# FMC_HPC1.net
KiCad netlist of a schematic drawn in Altium Designer
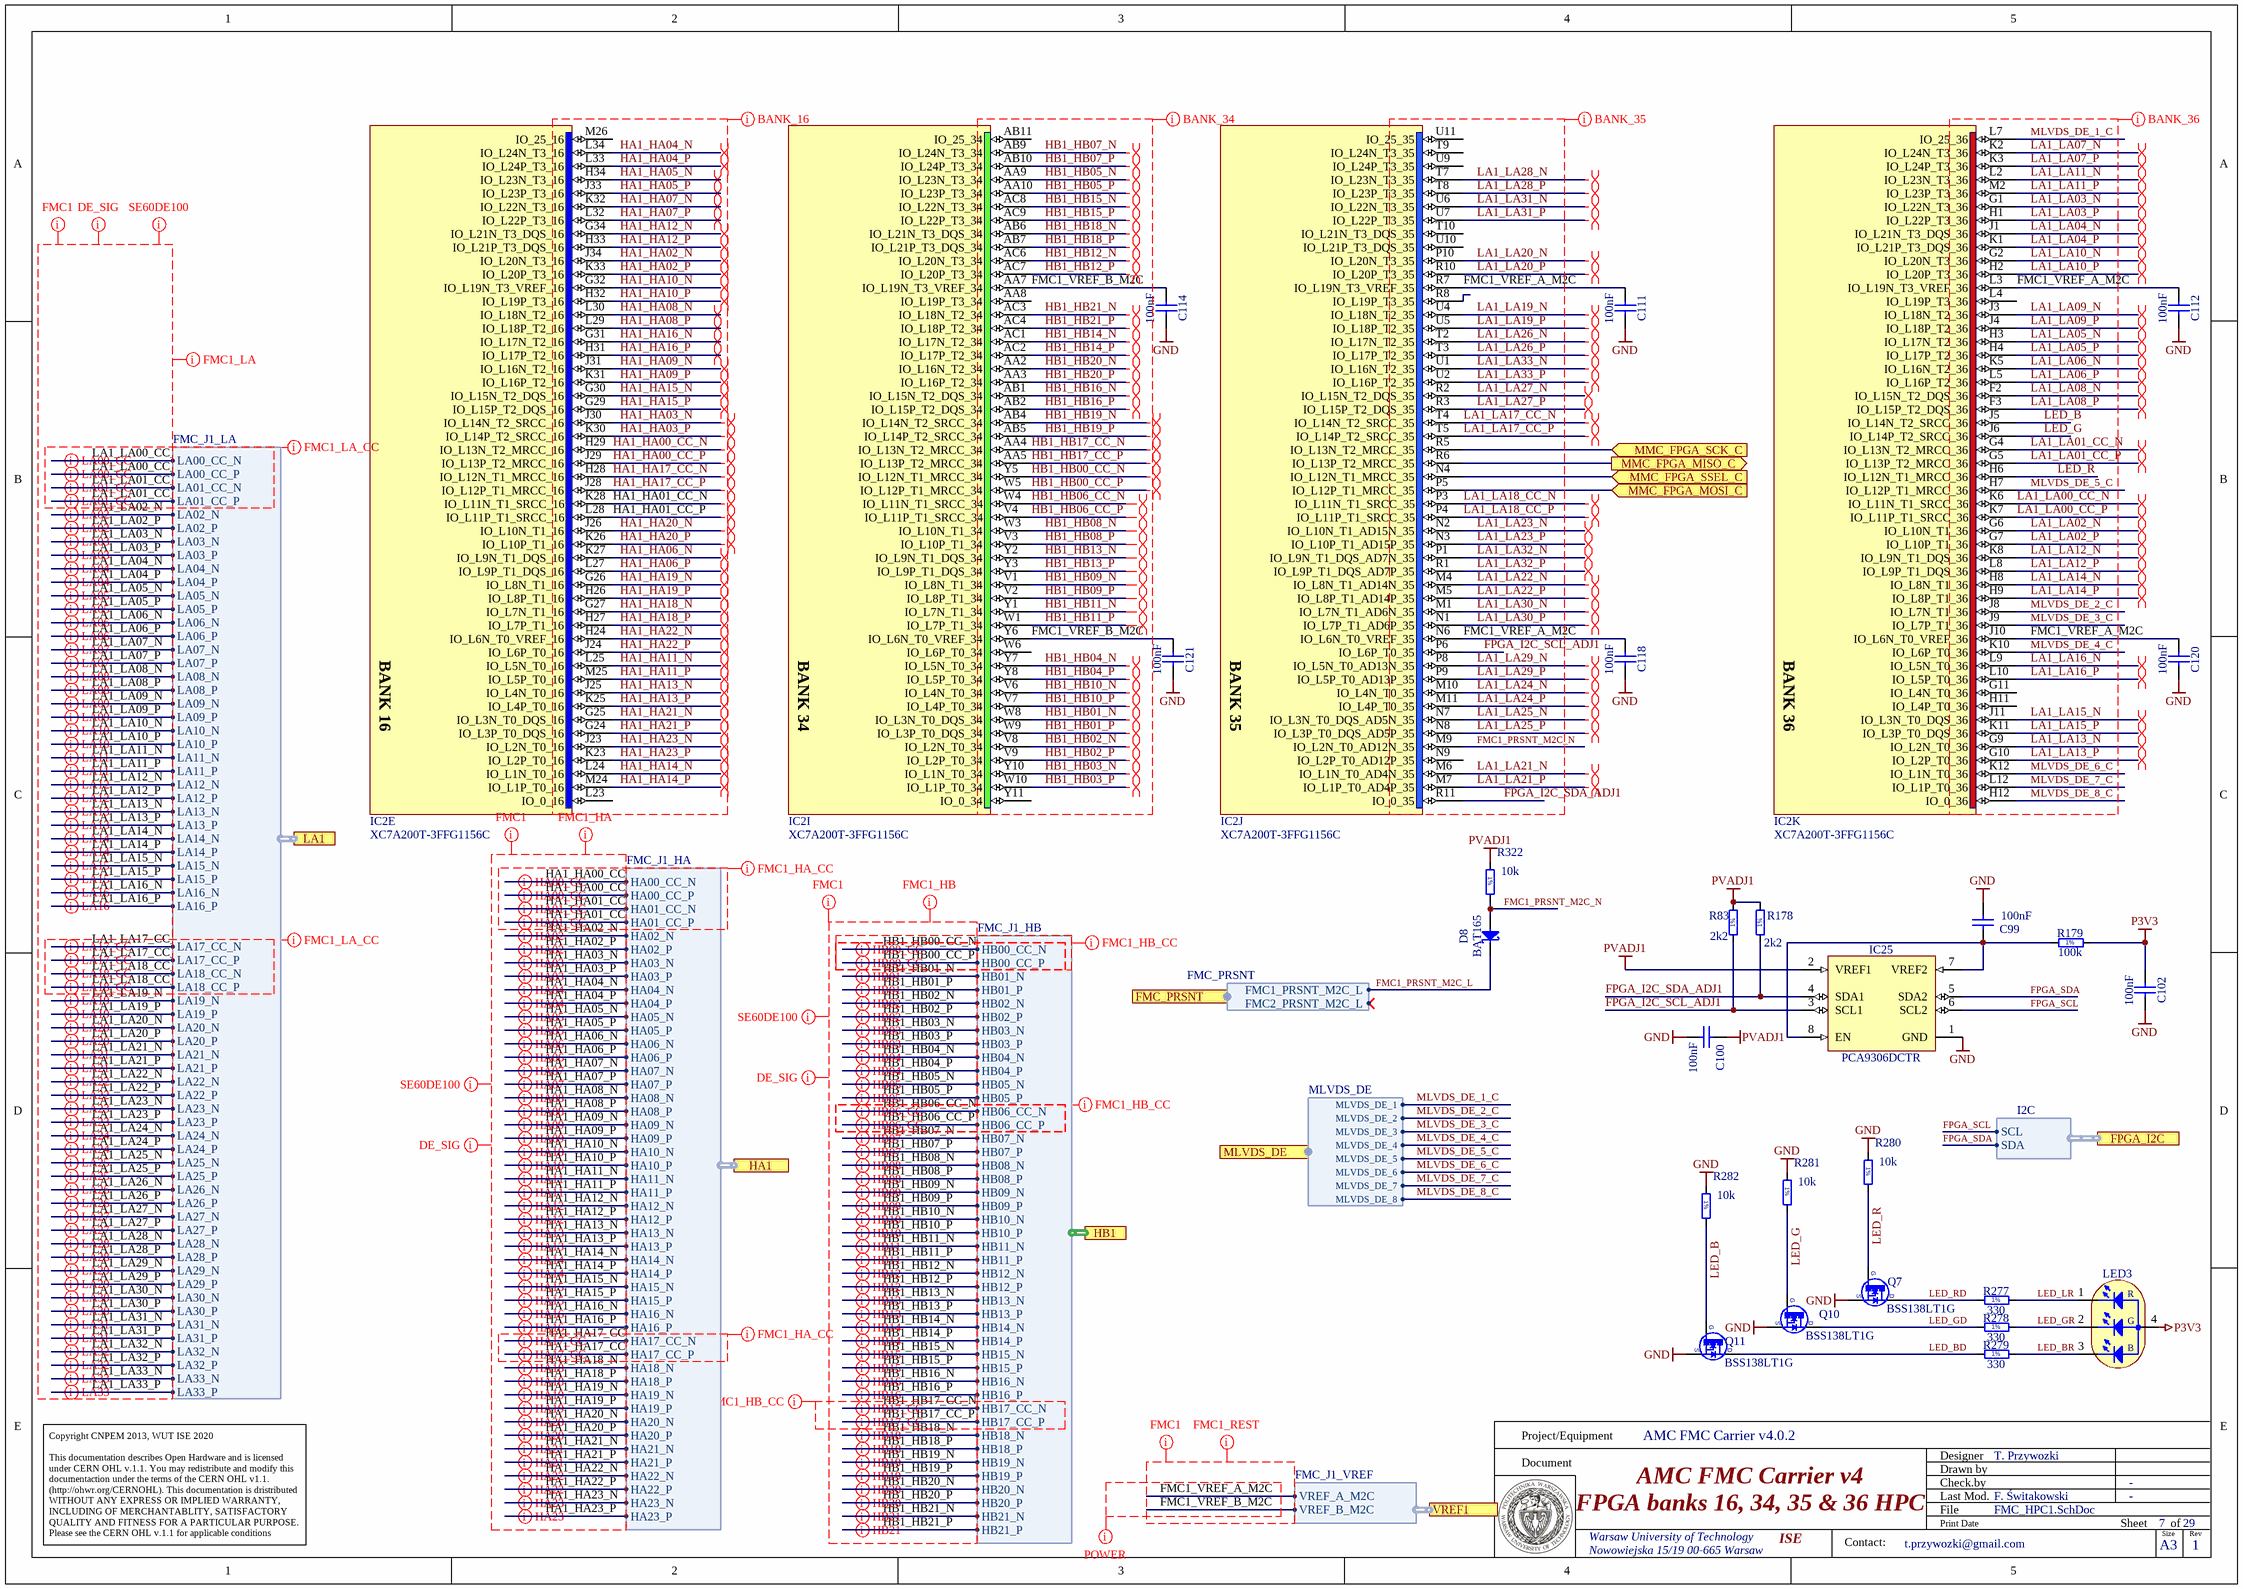
[diagram p0: FMC_HPC1.SchDoc]

(export (version "E")
  (design (tool "Eeschema 10.0.6"))
  (components
    (comp (ref "C99")
      (value "100nF")
      (footprint "CAPC0603X33N")
      (description "Non-polarised capacitor")
      (fields
        (field (name "PART NUMBER") "CC0201_100NF_6.3V_10%_X5R")
        (field (name "VOLTAGE") "6.3V")
        (field (name "AUTHOR") "CERN DEM JLC")
      )
      (libsource (lib "Capacitors") (part "Capacitor - non polarized"))
    )
    (comp (ref "C100")
      (value "100nF")
      (footprint "CAPC0603X33N")
      (description "Non-polarised capacitor")
      (fields
        (field (name "PART NUMBER") "CC0201_100NF_6.3V_10%_X5R")
        (field (name "VOLTAGE") "6.3V")
        (field (name "AUTHOR") "CERN DEM JLC")
      )
      (libsource (lib "Capacitors") (part "Capacitor - non polarized"))
    )
    (comp (ref "C102")
      (value "100nF")
      (footprint "CAPC0603X33N")
      (description "Non-polarised capacitor")
      (fields
        (field (name "PART NUMBER") "CC0201_100NF_6.3V_10%_X5R")
        (field (name "VOLTAGE") "6.3V")
        (field (name "AUTHOR") "CERN DEM JLC")
      )
      (libsource (lib "Capacitors") (part "Capacitor - non polarized"))
    )
    (comp (ref "C111")
      (value "100nF")
      (footprint "CAPC0603X33N")
      (description "Non-polarised capacitor")
      (fields
        (field (name "PART NUMBER") "CC0201_100NF_6.3V_10%_X5R")
        (field (name "VOLTAGE") "6.3V")
        (field (name "AUTHOR") "CERN DEM JLC")
      )
      (libsource (lib "Capacitors") (part "Capacitor - non polarized"))
    )
    (comp (ref "C112")
      (value "100nF")
      (footprint "CAPC0603X33N")
      (description "Non-polarised capacitor")
      (fields
        (field (name "PART NUMBER") "CC0201_100NF_6.3V_10%_X5R")
        (field (name "VOLTAGE") "6.3V")
        (field (name "AUTHOR") "CERN DEM JLC")
      )
      (libsource (lib "Capacitors") (part "Capacitor - non polarized"))
    )
    (comp (ref "C114")
      (value "100nF")
      (footprint "CAPC0603X33N")
      (description "Non-polarised capacitor")
      (fields
        (field (name "PART NUMBER") "CC0201_100NF_6.3V_10%_X5R")
        (field (name "VOLTAGE") "6.3V")
        (field (name "AUTHOR") "CERN DEM JLC")
      )
      (libsource (lib "Capacitors") (part "Capacitor - non polarized"))
    )
    (comp (ref "C118")
      (value "100nF")
      (footprint "CAPC0603X33N")
      (description "Non-polarised capacitor")
      (fields
        (field (name "PART NUMBER") "CC0201_100NF_6.3V_10%_X5R")
        (field (name "VOLTAGE") "6.3V")
        (field (name "AUTHOR") "CERN DEM JLC")
      )
      (libsource (lib "Capacitors") (part "Capacitor - non polarized"))
    )
    (comp (ref "C120")
      (value "100nF")
      (footprint "CAPC0603X33N")
      (description "Non-polarised capacitor")
      (fields
        (field (name "PART NUMBER") "CC0201_100NF_6.3V_10%_X5R")
        (field (name "VOLTAGE") "6.3V")
        (field (name "AUTHOR") "CERN DEM JLC")
      )
      (libsource (lib "Capacitors") (part "Capacitor - non polarized"))
    )
    (comp (ref "C121")
      (value "100nF")
      (footprint "CAPC0603X33N")
      (description "Non-polarised capacitor")
      (fields
        (field (name "PART NUMBER") "CC0201_100NF_6.3V_10%_X5R")
        (field (name "VOLTAGE") "6.3V")
        (field (name "AUTHOR") "CERN DEM JLC")
      )
      (libsource (lib "Capacitors") (part "Capacitor - non polarized"))
    )
    (comp (ref "D8")
      (value "BAT165")
      (footprint "SOD2512X110N")
      (description "Schottky Diode")
      (fields
        (field (name "MANUFACTURER") "INFINEON")
        (field (name "VOLTAGE") "40V")
        (field (name "AUTHOR") "CERN DEM JLC")
      )
      (libsource (lib "ICs And Semiconductors") (part "Diode Schottky"))
    )
    (comp (ref "IC2")
      (value "XC7A200T-3FFG1156C")
      (footprint "BGA1156C100P34X34_3500X3500X335")
      (description "Artix-6 FPGA, 16 GTPs, 600 User I/Os, 1156-Pin BGA, Speed Grade 2, Commercial Grade, Pb-Free")
      (fields
        (field (name "MANUFACTURER") "XILINX")
        (field (name "MANUFACTURER PART NUMBER") "XC7A350T-2FFG1156C")
        (field (name "AUTHOR") "CERN DEM JLC")
      )
      (libsource (lib "AMC_FMC_Carrier") (part "XC7A200T-3FFG1156C"))
    )
    (comp (ref "IC25")
      (value "PCA9306DCTR")
      (footprint "SOP65P400X130-8N")
      (description "Dual Bidirectional I2C Bus And SMBus Voltage-Level Translator")
      (fields (field (name "MANUFACTURER") "TEXAS INSTRUMENTS") (field (name "AUTHOR") "CERN DEM JLC"))
      (libsource (lib "ICs And Semiconductors") (part "PCA9306DC"))
    )
    (comp (ref "LED3")
      (value "Red/Green/Blue")
      (footprint "LED_OPTEK_OVSRRGBCC3_a")
      (description "Right Angle Tricolor (RGB) Surface Mount LED, Body 3.2x1mm")
      (fields
        (field (name "PART NUMBER") "LED_OPTEK_OVSRRGBCC3_a")
        (field (name "MANUFACTURER") "OPTEK / TT ELECTRONICS")
        (field (name "AUTHOR") "CERN DEM JLC")
      )
      (libsource (lib "ICs And Semiconductors") (part "LED_OPTEK_OVSRRGBCC3"))
    )
    (comp (ref "Q7")
      (value "BSS138LT1G")
      (footprint "SOT95P240X110-3N")
      (description "N-CHANNEL MOSFET WITH DIODE")
      (fields (field (name "MANUFACTURER") "ON SEMICONDUCTOR") (field (name "AUTHOR") "CERN DEM JLC"))
      (libsource (lib "ICs And Semiconductors") (part "N-MOSFET-D 1G 2S 3D"))
    )
    (comp (ref "Q10")
      (value "BSS138LT1G")
      (footprint "SOT95P240X110-3N")
      (description "N-CHANNEL MOSFET WITH DIODE")
      (fields (field (name "MANUFACTURER") "ON SEMICONDUCTOR") (field (name "AUTHOR") "CERN DEM JLC"))
      (libsource (lib "ICs And Semiconductors") (part "N-MOSFET-D 1G 2S 3D"))
    )
    (comp (ref "Q11")
      (value "BSS138LT1G")
      (footprint "SOT95P240X110-3N")
      (description "N-CHANNEL MOSFET WITH DIODE")
      (fields (field (name "MANUFACTURER") "ON SEMICONDUCTOR") (field (name "AUTHOR") "CERN DEM JLC"))
      (libsource (lib "ICs And Semiconductors") (part "N-MOSFET-D 1G 2S 3D"))
    )
    (comp (ref "R83")
      (value "2k2")
      (footprint "RESC1005X40N")
      (description "Resistor - 1%")
      (fields
        (field (name "PART NUMBER") "R0402_2K2_1%_0.0625W_100PPM")
        (field (name "POWER") "0.0625W")
        (field (name "AUTHOR") "CERN DEM JLC")
      )
      (libsource (lib "Resistors") (part "Resistor - 1%"))
    )
    (comp (ref "R178")
      (value "2k2")
      (footprint "RESC1005X40N")
      (description "Resistor - 1%")
      (fields
        (field (name "PART NUMBER") "R0402_2K2_1%_0.0625W_100PPM")
        (field (name "POWER") "0.0625W")
        (field (name "AUTHOR") "CERN DEM JLC")
      )
      (libsource (lib "Resistors") (part "Resistor - 1%"))
    )
    (comp (ref "R179")
      (value "100k")
      (footprint "RESC1005X40N")
      (description "Resistor - 1%")
      (fields
        (field (name "PART NUMBER") "R0402_100K_1%_0.0625W_100PPM")
        (field (name "POWER") "0.0625W")
        (field (name "AUTHOR") "CERN DEM JLC")
      )
      (libsource (lib "Resistors") (part "Resistor - 1%"))
    )
    (comp (ref "R277")
      (value "330")
      (footprint "RESC1005X40N")
      (description "Resistor - 1%")
      (fields
        (field (name "PART NUMBER") "R0402_330R_1%_0.0625W_100PPM")
        (field (name "POWER") "0.0625W")
        (field (name "AUTHOR") "CERN DEM JLC")
      )
      (libsource (lib "Resistors") (part "Resistor - 1%"))
    )
    (comp (ref "R278")
      (value "330")
      (footprint "RESC1005X40N")
      (description "Resistor - 1%")
      (fields
        (field (name "PART NUMBER") "R0402_330R_1%_0.0625W_100PPM")
        (field (name "POWER") "0.0625W")
        (field (name "AUTHOR") "CERN DEM JLC")
      )
      (libsource (lib "Resistors") (part "Resistor - 1%"))
    )
    (comp (ref "R279")
      (value "330")
      (footprint "RESC1005X40N")
      (description "Resistor - 1%")
      (fields
        (field (name "PART NUMBER") "R0402_330R_1%_0.0625W_100PPM")
        (field (name "POWER") "0.0625W")
        (field (name "AUTHOR") "CERN DEM JLC")
      )
      (libsource (lib "Resistors") (part "Resistor - 1%"))
    )
    (comp (ref "R280")
      (value "10k")
      (footprint "RESC1005X40N")
      (description "Resistor - 1%")
      (fields
        (field (name "PART NUMBER") "R0402_10K_1%_0.0625W_100PPM")
        (field (name "POWER") "0.0625W")
        (field (name "AUTHOR") "CERN DEM JLC")
      )
      (libsource (lib "Resistors") (part "Resistor - 1%"))
    )
    (comp (ref "R281")
      (value "10k")
      (footprint "RESC1005X40N")
      (description "Resistor - 1%")
      (fields
        (field (name "PART NUMBER") "R0402_10K_1%_0.0625W_100PPM")
        (field (name "POWER") "0.0625W")
        (field (name "AUTHOR") "CERN DEM JLC")
      )
      (libsource (lib "Resistors") (part "Resistor - 1%"))
    )
    (comp (ref "R282")
      (value "10k")
      (footprint "RESC1005X40N")
      (description "Resistor - 1%")
      (fields
        (field (name "PART NUMBER") "R0402_10K_1%_0.0625W_100PPM")
        (field (name "POWER") "0.0625W")
        (field (name "AUTHOR") "CERN DEM JLC")
      )
      (libsource (lib "Resistors") (part "Resistor - 1%"))
    )
    (comp (ref "R322")
      (value "10k")
      (footprint "RESC1005X40N")
      (description "Resistor - 1%")
      (fields
        (field (name "PART NUMBER") "R0402_10K_1%_0.0625W_100PPM")
        (field (name "POWER") "0.0625W")
        (field (name "AUTHOR") "CERN DEM JLC")
      )
      (libsource (lib "Resistors") (part "Resistor - 1%"))
    )
  )
  (nets
    (net (code "8") (name "/FMC1_PRSNT_M2C_L") (class "Default")
      (node (ref "D8") (pin "1") (pinfunction "C_1") (pintype "passive"))
    )
    (net (code "9") (name "/FMC1_PRSNT_M2C_N") (class "Default")
      (node (ref "D8") (pin "2") (pinfunction "A_2") (pintype "passive"))
      (node (ref "IC2") (pin "M9") (pinfunction "IO_L2N_T0_AD12N_35_M9") (pintype "bidirectional"))
      (node (ref "R322") (pin "2") (pinfunction "2_2") (pintype "passive"))
    )
    (net (code "10") (name "/FMC1_VREF_A_M2C") (class "Default")
      (node (ref "C111") (pin "1") (pinfunction "1_1") (pintype "passive"))
      (node (ref "C112") (pin "1") (pinfunction "1_1") (pintype "passive"))
      (node (ref "C118") (pin "1") (pinfunction "1_1") (pintype "passive"))
      (node (ref "C120") (pin "1") (pinfunction "1_1") (pintype "passive"))
      (node (ref "IC2") (pin "J10") (pinfunction "IO_L6N_T0_VREF_36_J10") (pintype "bidirectional"))
      (node (ref "IC2") (pin "L3") (pinfunction "IO_L19N_T3_VREF_36_L3") (pintype "bidirectional"))
      (node (ref "IC2") (pin "N6") (pinfunction "IO_L6N_T0_VREF_35_N6") (pintype "bidirectional"))
      (node (ref "IC2") (pin "R7") (pinfunction "IO_L19N_T3_VREF_35_R7") (pintype "bidirectional"))
    )
    (net (code "11") (name "/FMC1_VREF_B_M2C") (class "Default")
      (node (ref "C114") (pin "1") (pinfunction "1_1") (pintype "passive"))
      (node (ref "C121") (pin "1") (pinfunction "1_1") (pintype "passive"))
      (node (ref "IC2") (pin "AA7") (pinfunction "IO_L19N_T3_VREF_34_AA7") (pintype "bidirectional"))
      (node (ref "IC2") (pin "Y6") (pinfunction "IO_L6N_T0_VREF_34_Y6") (pintype "bidirectional"))
    )
    (net (code "12") (name "/FPGA_I2C_SCL_ADJ1") (class "Default")
      (node (ref "IC2") (pin "P6") (pinfunction "IO_L6P_T0_35_P6") (pintype "bidirectional"))
      (node (ref "IC25") (pin "3") (pinfunction "SCL1_3") (pintype "bidirectional"))
      (node (ref "R83") (pin "1") (pinfunction "1_1") (pintype "passive"))
    )
    (net (code "13") (name "/FPGA_I2C_SDA_ADJ1") (class "Default")
      (node (ref "IC2") (pin "R11") (pinfunction "IO_0_35_R11") (pintype "bidirectional"))
      (node (ref "IC25") (pin "4") (pinfunction "SDA1_4") (pintype "bidirectional"))
      (node (ref "R178") (pin "1") (pinfunction "1_1") (pintype "passive"))
    )
    (net (code "14") (name "/FPGA_SCL") (class "Default")
      (node (ref "IC25") (pin "6") (pinfunction "SCL2_6") (pintype "bidirectional"))
    )
    (net (code "15") (name "/FPGA_SDA") (class "Default")
      (node (ref "IC25") (pin "5") (pinfunction "SDA2_5") (pintype "bidirectional"))
    )
    (net (code "16") (name "/HA1_HA00_CC_N") (class "Default")
      (node (ref "IC2") (pin "H29") (pinfunction "IO_L13N_T2_MRCC_16_H29") (pintype "bidirectional"))
    )
    (net (code "17") (name "/HA1_HA00_CC_P") (class "Default")
      (node (ref "IC2") (pin "J29") (pinfunction "IO_L13P_T2_MRCC_16_J29") (pintype "bidirectional"))
    )
    (net (code "18") (name "/HA1_HA01_CC_N") (class "Default")
      (node (ref "IC2") (pin "K28") (pinfunction "IO_L11N_T1_SRCC_16_K28") (pintype "bidirectional"))
    )
    (net (code "19") (name "/HA1_HA01_CC_P") (class "Default")
      (node (ref "IC2") (pin "L28") (pinfunction "IO_L11P_T1_SRCC_16_L28") (pintype "bidirectional"))
    )
    (net (code "20") (name "/HA1_HA02_N") (class "Default")
      (node (ref "IC2") (pin "J34") (pinfunction "IO_L20N_T3_16_J34") (pintype "bidirectional"))
    )
    (net (code "21") (name "/HA1_HA02_P") (class "Default")
      (node (ref "IC2") (pin "K33") (pinfunction "IO_L20P_T3_16_K33") (pintype "bidirectional"))
    )
    (net (code "22") (name "/HA1_HA03_N") (class "Default")
      (node (ref "IC2") (pin "J30") (pinfunction "IO_L14N_T2_SRCC_16_J30") (pintype "bidirectional"))
    )
    (net (code "23") (name "/HA1_HA03_P") (class "Default")
      (node (ref "IC2") (pin "K30") (pinfunction "IO_L14P_T2_SRCC_16_K30") (pintype "bidirectional"))
    )
    (net (code "24") (name "/HA1_HA04_N") (class "Default")
      (node (ref "IC2") (pin "L34") (pinfunction "IO_L24N_T3_16_L34") (pintype "bidirectional"))
    )
    (net (code "25") (name "/HA1_HA04_P") (class "Default")
      (node (ref "IC2") (pin "L33") (pinfunction "IO_L24P_T3_16_L33") (pintype "bidirectional"))
    )
    (net (code "26") (name "/HA1_HA05_N") (class "Default")
      (node (ref "IC2") (pin "H34") (pinfunction "IO_L23N_T3_16_H34") (pintype "bidirectional"))
    )
    (net (code "27") (name "/HA1_HA05_P") (class "Default")
      (node (ref "IC2") (pin "J33") (pinfunction "IO_L23P_T3_16_J33") (pintype "bidirectional"))
    )
    (net (code "28") (name "/HA1_HA06_N") (class "Default")
      (node (ref "IC2") (pin "K27") (pinfunction "IO_L9N_T1_DQS_16_K27") (pintype "bidirectional"))
    )
    (net (code "29") (name "/HA1_HA06_P") (class "Default")
      (node (ref "IC2") (pin "L27") (pinfunction "IO_L9P_T1_DQS_16_L27") (pintype "bidirectional"))
    )
    (net (code "30") (name "/HA1_HA07_N") (class "Default")
      (node (ref "IC2") (pin "K32") (pinfunction "IO_L22N_T3_16_K32") (pintype "bidirectional"))
    )
    (net (code "31") (name "/HA1_HA07_P") (class "Default")
      (node (ref "IC2") (pin "L32") (pinfunction "IO_L22P_T3_16_L32") (pintype "bidirectional"))
    )
    (net (code "32") (name "/HA1_HA08_N") (class "Default")
      (node (ref "IC2") (pin "L30") (pinfunction "IO_L18N_T2_16_L30") (pintype "bidirectional"))
    )
    (net (code "33") (name "/HA1_HA08_P") (class "Default")
      (node (ref "IC2") (pin "L29") (pinfunction "IO_L18P_T2_16_L29") (pintype "bidirectional"))
    )
    (net (code "34") (name "/HA1_HA09_N") (class "Default")
      (node (ref "IC2") (pin "J31") (pinfunction "IO_L16N_T2_16_J31") (pintype "bidirectional"))
    )
    (net (code "35") (name "/HA1_HA09_P") (class "Default")
      (node (ref "IC2") (pin "K31") (pinfunction "IO_L16P_T2_16_K31") (pintype "bidirectional"))
    )
    (net (code "36") (name "/HA1_HA10_N") (class "Default")
      (node (ref "IC2") (pin "G32") (pinfunction "IO_L19N_T3_VREF_16_G32") (pintype "bidirectional"))
    )
    (net (code "37") (name "/HA1_HA10_P") (class "Default")
      (node (ref "IC2") (pin "H32") (pinfunction "IO_L19P_T3_16_H32") (pintype "bidirectional"))
    )
    (net (code "38") (name "/HA1_HA11_N") (class "Default")
      (node (ref "IC2") (pin "L25") (pinfunction "IO_L5N_T0_16_L25") (pintype "bidirectional"))
    )
    (net (code "39") (name "/HA1_HA11_P") (class "Default")
      (node (ref "IC2") (pin "M25") (pinfunction "IO_L5P_T0_16_M25") (pintype "bidirectional"))
    )
    (net (code "40") (name "/HA1_HA12_N") (class "Default")
      (node (ref "IC2") (pin "G34") (pinfunction "IO_L21N_T3_DQS_16_G34") (pintype "bidirectional"))
    )
    (net (code "41") (name "/HA1_HA12_P") (class "Default")
      (node (ref "IC2") (pin "H33") (pinfunction "IO_L21P_T3_DQS_16_H33") (pintype "bidirectional"))
    )
    (net (code "42") (name "/HA1_HA13_N") (class "Default")
      (node (ref "IC2") (pin "J25") (pinfunction "IO_L4N_T0_16_J25") (pintype "bidirectional"))
    )
    (net (code "43") (name "/HA1_HA13_P") (class "Default")
      (node (ref "IC2") (pin "K25") (pinfunction "IO_L4P_T0_16_K25") (pintype "bidirectional"))
    )
    (net (code "44") (name "/HA1_HA14_N") (class "Default")
      (node (ref "IC2") (pin "L24") (pinfunction "IO_L1N_T0_16_L24") (pintype "bidirectional"))
    )
    (net (code "45") (name "/HA1_HA14_P") (class "Default")
      (node (ref "IC2") (pin "M24") (pinfunction "IO_L1P_T0_16_M24") (pintype "bidirectional"))
    )
    (net (code "46") (name "/HA1_HA15_N") (class "Default")
      (node (ref "IC2") (pin "G30") (pinfunction "IO_L15N_T2_DQS_16_G30") (pintype "bidirectional"))
    )
    (net (code "47") (name "/HA1_HA15_P") (class "Default")
      (node (ref "IC2") (pin "G29") (pinfunction "IO_L15P_T2_DQS_16_G29") (pintype "bidirectional"))
    )
    (net (code "48") (name "/HA1_HA16_N") (class "Default")
      (node (ref "IC2") (pin "G31") (pinfunction "IO_L17N_T2_16_G31") (pintype "bidirectional"))
    )
    (net (code "49") (name "/HA1_HA16_P") (class "Default")
      (node (ref "IC2") (pin "H31") (pinfunction "IO_L17P_T2_16_H31") (pintype "bidirectional"))
    )
    (net (code "50") (name "/HA1_HA17_CC_N") (class "Default")
      (node (ref "IC2") (pin "H28") (pinfunction "IO_L12N_T1_MRCC_16_H28") (pintype "bidirectional"))
    )
    (net (code "51") (name "/HA1_HA17_CC_P") (class "Default")
      (node (ref "IC2") (pin "J28") (pinfunction "IO_L12P_T1_MRCC_16_J28") (pintype "bidirectional"))
    )
    (net (code "52") (name "/HA1_HA18_N") (class "Default")
      (node (ref "IC2") (pin "G27") (pinfunction "IO_L7N_T1_16_G27") (pintype "bidirectional"))
    )
    (net (code "53") (name "/HA1_HA18_P") (class "Default")
      (node (ref "IC2") (pin "H27") (pinfunction "IO_L7P_T1_16_H27") (pintype "bidirectional"))
    )
    (net (code "54") (name "/HA1_HA19_N") (class "Default")
      (node (ref "IC2") (pin "G26") (pinfunction "IO_L8N_T1_16_G26") (pintype "bidirectional"))
    )
    (net (code "55") (name "/HA1_HA19_P") (class "Default")
      (node (ref "IC2") (pin "H26") (pinfunction "IO_L8P_T1_16_H26") (pintype "bidirectional"))
    )
    (net (code "56") (name "/HA1_HA20_N") (class "Default")
      (node (ref "IC2") (pin "J26") (pinfunction "IO_L10N_T1_16_J26") (pintype "bidirectional"))
    )
    (net (code "57") (name "/HA1_HA20_P") (class "Default")
      (node (ref "IC2") (pin "K26") (pinfunction "IO_L10P_T1_16_K26") (pintype "bidirectional"))
    )
    (net (code "58") (name "/HA1_HA21_N") (class "Default")
      (node (ref "IC2") (pin "G25") (pinfunction "IO_L3N_T0_DQS_16_G25") (pintype "bidirectional"))
    )
    (net (code "59") (name "/HA1_HA21_P") (class "Default")
      (node (ref "IC2") (pin "G24") (pinfunction "IO_L3P_T0_DQS_16_G24") (pintype "bidirectional"))
    )
    (net (code "60") (name "/HA1_HA22_N") (class "Default")
      (node (ref "IC2") (pin "H24") (pinfunction "IO_L6N_T0_VREF_16_H24") (pintype "bidirectional"))
    )
    (net (code "61") (name "/HA1_HA22_P") (class "Default")
      (node (ref "IC2") (pin "J24") (pinfunction "IO_L6P_T0_16_J24") (pintype "bidirectional"))
    )
    (net (code "62") (name "/HA1_HA23_N") (class "Default")
      (node (ref "IC2") (pin "J23") (pinfunction "IO_L2N_T0_16_J23") (pintype "bidirectional"))
    )
    (net (code "63") (name "/HA1_HA23_P") (class "Default")
      (node (ref "IC2") (pin "K23") (pinfunction "IO_L2P_T0_16_K23") (pintype "bidirectional"))
    )
    (net (code "64") (name "/HB1_HB00_CC_N") (class "Default")
      (node (ref "IC2") (pin "Y5") (pinfunction "IO_L12N_T1_MRCC_34_Y5") (pintype "bidirectional"))
    )
    (net (code "65") (name "/HB1_HB00_CC_P") (class "Default")
      (node (ref "IC2") (pin "W5") (pinfunction "IO_L12P_T1_MRCC_34_W5") (pintype "bidirectional"))
    )
    (net (code "66") (name "/HB1_HB01_N") (class "Default")
      (node (ref "IC2") (pin "W8") (pinfunction "IO_L3N_T0_DQS_34_W8") (pintype "bidirectional"))
    )
    (net (code "67") (name "/HB1_HB01_P") (class "Default")
      (node (ref "IC2") (pin "W9") (pinfunction "IO_L3P_T0_DQS_34_W9") (pintype "bidirectional"))
    )
    (net (code "68") (name "/HB1_HB02_N") (class "Default")
      (node (ref "IC2") (pin "V8") (pinfunction "IO_L2N_T0_34_V8") (pintype "bidirectional"))
    )
    (net (code "69") (name "/HB1_HB02_P") (class "Default")
      (node (ref "IC2") (pin "V9") (pinfunction "IO_L2P_T0_34_V9") (pintype "bidirectional"))
    )
    (net (code "70") (name "/HB1_HB03_N") (class "Default")
      (node (ref "IC2") (pin "Y10") (pinfunction "IO_L1N_T0_34_Y10") (pintype "bidirectional"))
    )
    (net (code "71") (name "/HB1_HB03_P") (class "Default")
      (node (ref "IC2") (pin "W10") (pinfunction "IO_L1P_T0_34_W10") (pintype "bidirectional"))
    )
    (net (code "72") (name "/HB1_HB04_N") (class "Default")
      (node (ref "IC2") (pin "Y7") (pinfunction "IO_L5N_T0_34_Y7") (pintype "bidirectional"))
    )
    (net (code "73") (name "/HB1_HB04_P") (class "Default")
      (node (ref "IC2") (pin "Y8") (pinfunction "IO_L5P_T0_34_Y8") (pintype "bidirectional"))
    )
    (net (code "74") (name "/HB1_HB05_N") (class "Default")
      (node (ref "IC2") (pin "AA9") (pinfunction "IO_L23N_T3_34_AA9") (pintype "bidirectional"))
    )
    (net (code "75") (name "/HB1_HB05_P") (class "Default")
      (node (ref "IC2") (pin "AA10") (pinfunction "IO_L23P_T3_34_AA10") (pintype "bidirectional"))
    )
    (net (code "76") (name "/HB1_HB06_CC_N") (class "Default")
      (node (ref "IC2") (pin "W4") (pinfunction "IO_L11N_T1_SRCC_34_W4") (pintype "bidirectional"))
    )
    (net (code "77") (name "/HB1_HB06_CC_P") (class "Default")
      (node (ref "IC2") (pin "V4") (pinfunction "IO_L11P_T1_SRCC_34_V4") (pintype "bidirectional"))
    )
    (net (code "78") (name "/HB1_HB07_N") (class "Default")
      (node (ref "IC2") (pin "AB9") (pinfunction "IO_L24N_T3_34_AB9") (pintype "bidirectional"))
    )
    (net (code "79") (name "/HB1_HB07_P") (class "Default")
      (node (ref "IC2") (pin "AB10") (pinfunction "IO_L24P_T3_34_AB10") (pintype "bidirectional"))
    )
    (net (code "80") (name "/HB1_HB08_N") (class "Default")
      (node (ref "IC2") (pin "W3") (pinfunction "IO_L10N_T1_34_W3") (pintype "bidirectional"))
    )
    (net (code "81") (name "/HB1_HB08_P") (class "Default")
      (node (ref "IC2") (pin "V3") (pinfunction "IO_L10P_T1_34_V3") (pintype "bidirectional"))
    )
    (net (code "82") (name "/HB1_HB09_N") (class "Default")
      (node (ref "IC2") (pin "V1") (pinfunction "IO_L8N_T1_34_V1") (pintype "bidirectional"))
    )
    (net (code "83") (name "/HB1_HB09_P") (class "Default")
      (node (ref "IC2") (pin "V2") (pinfunction "IO_L8P_T1_34_V2") (pintype "bidirectional"))
    )
    (net (code "84") (name "/HB1_HB10_N") (class "Default")
      (node (ref "IC2") (pin "V6") (pinfunction "IO_L4N_T0_34_V6") (pintype "bidirectional"))
    )
    (net (code "85") (name "/HB1_HB10_P") (class "Default")
      (node (ref "IC2") (pin "V7") (pinfunction "IO_L4P_T0_34_V7") (pintype "bidirectional"))
    )
    (net (code "86") (name "/HB1_HB11_N") (class "Default")
      (node (ref "IC2") (pin "Y1") (pinfunction "IO_L7N_T1_34_Y1") (pintype "bidirectional"))
    )
    (net (code "87") (name "/HB1_HB11_P") (class "Default")
      (node (ref "IC2") (pin "W1") (pinfunction "IO_L7P_T1_34_W1") (pintype "bidirectional"))
    )
    (net (code "88") (name "/HB1_HB12_N") (class "Default")
      (node (ref "IC2") (pin "AC6") (pinfunction "IO_L20N_T3_34_AC6") (pintype "bidirectional"))
    )
    (net (code "89") (name "/HB1_HB12_P") (class "Default")
      (node (ref "IC2") (pin "AC7") (pinfunction "IO_L20P_T3_34_AC7") (pintype "bidirectional"))
    )
    (net (code "90") (name "/HB1_HB13_N") (class "Default")
      (node (ref "IC2") (pin "Y2") (pinfunction "IO_L9N_T1_DQS_34_Y2") (pintype "bidirectional"))
    )
    (net (code "91") (name "/HB1_HB13_P") (class "Default")
      (node (ref "IC2") (pin "Y3") (pinfunction "IO_L9P_T1_DQS_34_Y3") (pintype "bidirectional"))
    )
    (net (code "92") (name "/HB1_HB14_N") (class "Default")
      (node (ref "IC2") (pin "AC1") (pinfunction "IO_L17N_T2_34_AC1") (pintype "bidirectional"))
    )
    (net (code "93") (name "/HB1_HB14_P") (class "Default")
      (node (ref "IC2") (pin "AC2") (pinfunction "IO_L17P_T2_34_AC2") (pintype "bidirectional"))
    )
    (net (code "94") (name "/HB1_HB15_N") (class "Default")
      (node (ref "IC2") (pin "AC8") (pinfunction "IO_L22N_T3_34_AC8") (pintype "bidirectional"))
    )
    (net (code "95") (name "/HB1_HB15_P") (class "Default")
      (node (ref "IC2") (pin "AC9") (pinfunction "IO_L22P_T3_34_AC9") (pintype "bidirectional"))
    )
    (net (code "96") (name "/HB1_HB16_N") (class "Default")
      (node (ref "IC2") (pin "AB1") (pinfunction "IO_L15N_T2_DQS_34_AB1") (pintype "bidirectional"))
    )
    (net (code "97") (name "/HB1_HB16_P") (class "Default")
      (node (ref "IC2") (pin "AB2") (pinfunction "IO_L15P_T2_DQS_34_AB2") (pintype "bidirectional"))
    )
    (net (code "98") (name "/HB1_HB17_CC_N") (class "Default")
      (node (ref "IC2") (pin "AA4") (pinfunction "IO_L13N_T2_MRCC_34_AA4") (pintype "bidirectional"))
    )
    (net (code "99") (name "/HB1_HB17_CC_P") (class "Default")
      (node (ref "IC2") (pin "AA5") (pinfunction "IO_L13P_T2_MRCC_34_AA5") (pintype "bidirectional"))
    )
    (net (code "100") (name "/HB1_HB18_N") (class "Default")
      (node (ref "IC2") (pin "AB6") (pinfunction "IO_L21N_T3_DQS_34_AB6") (pintype "bidirectional"))
    )
    (net (code "101") (name "/HB1_HB18_P") (class "Default")
      (node (ref "IC2") (pin "AB7") (pinfunction "IO_L21P_T3_DQS_34_AB7") (pintype "bidirectional"))
    )
    (net (code "102") (name "/HB1_HB19_N") (class "Default")
      (node (ref "IC2") (pin "AB4") (pinfunction "IO_L14N_T2_SRCC_34_AB4") (pintype "bidirectional"))
    )
    (net (code "103") (name "/HB1_HB19_P") (class "Default")
      (node (ref "IC2") (pin "AB5") (pinfunction "IO_L14P_T2_SRCC_34_AB5") (pintype "bidirectional"))
    )
    (net (code "104") (name "/HB1_HB20_N") (class "Default")
      (node (ref "IC2") (pin "AA2") (pinfunction "IO_L16N_T2_34_AA2") (pintype "bidirectional"))
    )
    (net (code "105") (name "/HB1_HB20_P") (class "Default")
      (node (ref "IC2") (pin "AA3") (pinfunction "IO_L16P_T2_34_AA3") (pintype "bidirectional"))
    )
    (net (code "106") (name "/HB1_HB21_N") (class "Default")
      (node (ref "IC2") (pin "AC3") (pinfunction "IO_L18N_T2_34_AC3") (pintype "bidirectional"))
    )
    (net (code "107") (name "/HB1_HB21_P") (class "Default")
      (node (ref "IC2") (pin "AC4") (pinfunction "IO_L18P_T2_34_AC4") (pintype "bidirectional"))
    )
    (net (code "108") (name "/LA1_LA00_CC_N") (class "Default")
      (node (ref "IC2") (pin "K6") (pinfunction "IO_L11N_T1_SRCC_36_K6") (pintype "bidirectional"))
    )
    (net (code "109") (name "/LA1_LA00_CC_P") (class "Default")
      (node (ref "IC2") (pin "K7") (pinfunction "IO_L11P_T1_SRCC_36_K7") (pintype "bidirectional"))
    )
    (net (code "110") (name "/LA1_LA01_CC_N") (class "Default")
      (node (ref "IC2") (pin "G4") (pinfunction "IO_L13N_T2_MRCC_36_G4") (pintype "bidirectional"))
    )
    (net (code "111") (name "/LA1_LA01_CC_P") (class "Default")
      (node (ref "IC2") (pin "G5") (pinfunction "IO_L13P_T2_MRCC_36_G5") (pintype "bidirectional"))
    )
    (net (code "112") (name "/LA1_LA02_N") (class "Default")
      (node (ref "IC2") (pin "G6") (pinfunction "IO_L10N_T1_36_G6") (pintype "bidirectional"))
    )
    (net (code "113") (name "/LA1_LA02_P") (class "Default")
      (node (ref "IC2") (pin "G7") (pinfunction "IO_L10P_T1_36_G7") (pintype "bidirectional"))
    )
    (net (code "114") (name "/LA1_LA03_N") (class "Default")
      (node (ref "IC2") (pin "G1") (pinfunction "IO_L22N_T3_36_G1") (pintype "bidirectional"))
    )
    (net (code "115") (name "/LA1_LA03_P") (class "Default")
      (node (ref "IC2") (pin "H1") (pinfunction "IO_L22P_T3_36_H1") (pintype "bidirectional"))
    )
    (net (code "116") (name "/LA1_LA04_N") (class "Default")
      (node (ref "IC2") (pin "J1") (pinfunction "IO_L21N_T3_DQS_36_J1") (pintype "bidirectional"))
    )
    (net (code "117") (name "/LA1_LA04_P") (class "Default")
      (node (ref "IC2") (pin "K1") (pinfunction "IO_L21P_T3_DQS_36_K1") (pintype "bidirectional"))
    )
    (net (code "118") (name "/LA1_LA05_N") (class "Default")
      (node (ref "IC2") (pin "H3") (pinfunction "IO_L17N_T2_36_H3") (pintype "bidirectional"))
    )
    (net (code "119") (name "/LA1_LA05_P") (class "Default")
      (node (ref "IC2") (pin "H4") (pinfunction "IO_L17P_T2_36_H4") (pintype "bidirectional"))
    )
    (net (code "120") (name "/LA1_LA06_N") (class "Default")
      (node (ref "IC2") (pin "K5") (pinfunction "IO_L16N_T2_36_K5") (pintype "bidirectional"))
    )
    (net (code "121") (name "/LA1_LA06_P") (class "Default")
      (node (ref "IC2") (pin "L5") (pinfunction "IO_L16P_T2_36_L5") (pintype "bidirectional"))
    )
    (net (code "122") (name "/LA1_LA07_N") (class "Default")
      (node (ref "IC2") (pin "K2") (pinfunction "IO_L24N_T3_36_K2") (pintype "bidirectional"))
    )
    (net (code "123") (name "/LA1_LA07_P") (class "Default")
      (node (ref "IC2") (pin "K3") (pinfunction "IO_L24P_T3_36_K3") (pintype "bidirectional"))
    )
    (net (code "124") (name "/LA1_LA08_N") (class "Default")
      (node (ref "IC2") (pin "F2") (pinfunction "IO_L15N_T2_DQS_36_F2") (pintype "bidirectional"))
    )
    (net (code "125") (name "/LA1_LA08_P") (class "Default")
      (node (ref "IC2") (pin "F3") (pinfunction "IO_L15P_T2_DQS_36_F3") (pintype "bidirectional"))
    )
    (net (code "126") (name "/LA1_LA09_N") (class "Default")
      (node (ref "IC2") (pin "J3") (pinfunction "IO_L18N_T2_36_J3") (pintype "bidirectional"))
    )
    (net (code "127") (name "/LA1_LA09_P") (class "Default")
      (node (ref "IC2") (pin "J4") (pinfunction "IO_L18P_T2_36_J4") (pintype "bidirectional"))
    )
    (net (code "128") (name "/LA1_LA10_N") (class "Default")
      (node (ref "IC2") (pin "G2") (pinfunction "IO_L20N_T3_36_G2") (pintype "bidirectional"))
    )
    (net (code "129") (name "/LA1_LA10_P") (class "Default")
      (node (ref "IC2") (pin "H2") (pinfunction "IO_L20P_T3_36_H2") (pintype "bidirectional"))
    )
    (net (code "130") (name "/LA1_LA11_N") (class "Default")
      (node (ref "IC2") (pin "L2") (pinfunction "IO_L23N_T3_36_L2") (pintype "bidirectional"))
    )
    (net (code "131") (name "/LA1_LA11_P") (class "Default")
      (node (ref "IC2") (pin "M2") (pinfunction "IO_L23P_T3_36_M2") (pintype "bidirectional"))
    )
    (net (code "132") (name "/LA1_LA12_N") (class "Default")
      (node (ref "IC2") (pin "K8") (pinfunction "IO_L9N_T1_DQS_36_K8") (pintype "bidirectional"))
    )
    (net (code "133") (name "/LA1_LA12_P") (class "Default")
      (node (ref "IC2") (pin "L8") (pinfunction "IO_L9P_T1_DQS_36_L8") (pintype "bidirectional"))
    )
    (net (code "134") (name "/LA1_LA13_N") (class "Default")
      (node (ref "IC2") (pin "G9") (pinfunction "IO_L2N_T0_36_G9") (pintype "bidirectional"))
    )
    (net (code "135") (name "/LA1_LA13_P") (class "Default")
      (node (ref "IC2") (pin "G10") (pinfunction "IO_L2P_T0_36_G10") (pintype "bidirectional"))
    )
    (net (code "136") (name "/LA1_LA14_N") (class "Default")
      (node (ref "IC2") (pin "H8") (pinfunction "IO_L8N_T1_36_H8") (pintype "bidirectional"))
    )
    (net (code "137") (name "/LA1_LA14_P") (class "Default")
      (node (ref "IC2") (pin "H9") (pinfunction "IO_L8P_T1_36_H9") (pintype "bidirectional"))
    )
    (net (code "138") (name "/LA1_LA15_N") (class "Default")
      (node (ref "IC2") (pin "J11") (pinfunction "IO_L3N_T0_DQS_36_J11") (pintype "bidirectional"))
    )
    (net (code "139") (name "/LA1_LA15_P") (class "Default")
      (node (ref "IC2") (pin "K11") (pinfunction "IO_L3P_T0_DQS_36_K11") (pintype "bidirectional"))
    )
    (net (code "140") (name "/LA1_LA16_N") (class "Default")
      (node (ref "IC2") (pin "L9") (pinfunction "IO_L5N_T0_36_L9") (pintype "bidirectional"))
    )
    (net (code "141") (name "/LA1_LA16_P") (class "Default")
      (node (ref "IC2") (pin "L10") (pinfunction "IO_L5P_T0_36_L10") (pintype "bidirectional"))
    )
    (net (code "142") (name "/LA1_LA17_CC_N") (class "Default")
      (node (ref "IC2") (pin "T4") (pinfunction "IO_L14N_T2_SRCC_35_T4") (pintype "bidirectional"))
    )
    (net (code "143") (name "/LA1_LA17_CC_P") (class "Default")
      (node (ref "IC2") (pin "T5") (pinfunction "IO_L14P_T2_SRCC_35_T5") (pintype "bidirectional"))
    )
    (net (code "144") (name "/LA1_LA18_CC_N") (class "Default")
      (node (ref "IC2") (pin "P3") (pinfunction "IO_L11N_T1_SRCC_35_P3") (pintype "bidirectional"))
    )
    (net (code "145") (name "/LA1_LA18_CC_P") (class "Default")
      (node (ref "IC2") (pin "P4") (pinfunction "IO_L11P_T1_SRCC_35_P4") (pintype "bidirectional"))
    )
    (net (code "146") (name "/LA1_LA19_N") (class "Default")
      (node (ref "IC2") (pin "U4") (pinfunction "IO_L18N_T2_35_U4") (pintype "bidirectional"))
    )
    (net (code "147") (name "/LA1_LA19_P") (class "Default")
      (node (ref "IC2") (pin "U5") (pinfunction "IO_L18P_T2_35_U5") (pintype "bidirectional"))
    )
    (net (code "148") (name "/LA1_LA20_N") (class "Default")
      (node (ref "IC2") (pin "P10") (pinfunction "IO_L20N_T3_35_P10") (pintype "bidirectional"))
    )
    (net (code "149") (name "/LA1_LA20_P") (class "Default")
      (node (ref "IC2") (pin "R10") (pinfunction "IO_L20P_T3_35_R10") (pintype "bidirectional"))
    )
    (net (code "150") (name "/LA1_LA21_N") (class "Default")
      (node (ref "IC2") (pin "M6") (pinfunction "IO_L1N_T0_AD4N_35_M6") (pintype "bidirectional"))
    )
    (net (code "151") (name "/LA1_LA21_P") (class "Default")
      (node (ref "IC2") (pin "M7") (pinfunction "IO_L1P_T0_AD4P_35_M7") (pintype "bidirectional"))
    )
    (net (code "152") (name "/LA1_LA22_N") (class "Default")
      (node (ref "IC2") (pin "M4") (pinfunction "IO_L8N_T1_AD14N_35_M4") (pintype "bidirectional"))
    )
    (net (code "153") (name "/LA1_LA22_P") (class "Default")
      (node (ref "IC2") (pin "M5") (pinfunction "IO_L8P_T1_AD14P_35_M5") (pintype "bidirectional"))
    )
    (net (code "154") (name "/LA1_LA23_N") (class "Default")
      (node (ref "IC2") (pin "N2") (pinfunction "IO_L10N_T1_AD15N_35_N2") (pintype "bidirectional"))
    )
    (net (code "155") (name "/LA1_LA23_P") (class "Default")
      (node (ref "IC2") (pin "N3") (pinfunction "IO_L10P_T1_AD15P_35_N3") (pintype "bidirectional"))
    )
    (net (code "156") (name "/LA1_LA24_N") (class "Default")
      (node (ref "IC2") (pin "M10") (pinfunction "IO_L4N_T0_35_M10") (pintype "bidirectional"))
    )
    (net (code "157") (name "/LA1_LA24_P") (class "Default")
      (node (ref "IC2") (pin "M11") (pinfunction "IO_L4P_T0_35_M11") (pintype "bidirectional"))
    )
    (net (code "158") (name "/LA1_LA25_N") (class "Default")
      (node (ref "IC2") (pin "N7") (pinfunction "IO_L3N_T0_DQS_AD5N_35_N7") (pintype "bidirectional"))
    )
    (net (code "159") (name "/LA1_LA25_P") (class "Default")
      (node (ref "IC2") (pin "N8") (pinfunction "IO_L3P_T0_DQS_AD5P_35_N8") (pintype "bidirectional"))
    )
    (net (code "160") (name "/LA1_LA26_N") (class "Default")
      (node (ref "IC2") (pin "T2") (pinfunction "IO_L17N_T2_35_T2") (pintype "bidirectional"))
    )
    (net (code "161") (name "/LA1_LA26_P") (class "Default")
      (node (ref "IC2") (pin "T3") (pinfunction "IO_L17P_T2_35_T3") (pintype "bidirectional"))
    )
    (net (code "162") (name "/LA1_LA27_N") (class "Default")
      (node (ref "IC2") (pin "R2") (pinfunction "IO_L15N_T2_DQS_35_R2") (pintype "bidirectional"))
    )
    (net (code "163") (name "/LA1_LA27_P") (class "Default")
      (node (ref "IC2") (pin "R3") (pinfunction "IO_L15P_T2_DQS_35_R3") (pintype "bidirectional"))
    )
    (net (code "164") (name "/LA1_LA28_N") (class "Default")
      (node (ref "IC2") (pin "T7") (pinfunction "IO_L23N_T3_35_T7") (pintype "bidirectional"))
    )
    (net (code "165") (name "/LA1_LA28_P") (class "Default")
      (node (ref "IC2") (pin "T8") (pinfunction "IO_L23P_T3_35_T8") (pintype "bidirectional"))
    )
    (net (code "166") (name "/LA1_LA29_N") (class "Default")
      (node (ref "IC2") (pin "P8") (pinfunction "IO_L5N_T0_AD13N_35_P8") (pintype "bidirectional"))
    )
    (net (code "167") (name "/LA1_LA29_P") (class "Default")
      (node (ref "IC2") (pin "P9") (pinfunction "IO_L5P_T0_AD13P_35_P9") (pintype "bidirectional"))
    )
    (net (code "168") (name "/LA1_LA30_N") (class "Default")
      (node (ref "IC2") (pin "M1") (pinfunction "IO_L7N_T1_AD6N_35_M1") (pintype "bidirectional"))
    )
    (net (code "169") (name "/LA1_LA30_P") (class "Default")
      (node (ref "IC2") (pin "N1") (pinfunction "IO_L7P_T1_AD6P_35_N1") (pintype "bidirectional"))
    )
    (net (code "170") (name "/LA1_LA31_N") (class "Default")
      (node (ref "IC2") (pin "U6") (pinfunction "IO_L22N_T3_35_U6") (pintype "bidirectional"))
    )
    (net (code "171") (name "/LA1_LA31_P") (class "Default")
      (node (ref "IC2") (pin "U7") (pinfunction "IO_L22P_T3_35_U7") (pintype "bidirectional"))
    )
    (net (code "172") (name "/LA1_LA32_N") (class "Default")
      (node (ref "IC2") (pin "P1") (pinfunction "IO_L9N_T1_DQS_AD7N_35_P1") (pintype "bidirectional"))
    )
    (net (code "173") (name "/LA1_LA32_P") (class "Default")
      (node (ref "IC2") (pin "R1") (pinfunction "IO_L9P_T1_DQS_AD7P_35_R1") (pintype "bidirectional"))
    )
    (net (code "174") (name "/LA1_LA33_N") (class "Default")
      (node (ref "IC2") (pin "U1") (pinfunction "IO_L16N_T2_35_U1") (pintype "bidirectional"))
    )
    (net (code "175") (name "/LA1_LA33_P") (class "Default")
      (node (ref "IC2") (pin "U2") (pinfunction "IO_L16P_T2_35_U2") (pintype "bidirectional"))
    )
    (net (code "176") (name "/LED_B") (class "Default")
      (node (ref "IC2") (pin "J5") (pinfunction "IO_L14N_T2_SRCC_36_J5") (pintype "bidirectional"))
      (node (ref "Q11") (pin "1") (pinfunction "G_1") (pintype "passive"))
      (node (ref "R282") (pin "2") (pinfunction "2_2") (pintype "passive"))
    )
    (net (code "177") (name "/LED_BD") (class "Default")
      (node (ref "Q11") (pin "3") (pinfunction "D_3") (pintype "passive"))
      (node (ref "R279") (pin "1") (pinfunction "1_1") (pintype "passive"))
    )
    (net (code "178") (name "/LED_BR") (class "Default")
      (node (ref "LED3") (pin "3") (pinfunction "AB_3") (pintype "passive"))
      (node (ref "R279") (pin "2") (pinfunction "2_2") (pintype "passive"))
    )
    (net (code "179") (name "/LED_G") (class "Default")
      (node (ref "IC2") (pin "J6") (pinfunction "IO_L14P_T2_SRCC_36_J6") (pintype "bidirectional"))
      (node (ref "Q10") (pin "1") (pinfunction "G_1") (pintype "passive"))
      (node (ref "R281") (pin "2") (pinfunction "2_2") (pintype "passive"))
    )
    (net (code "180") (name "/LED_GD") (class "Default")
      (node (ref "Q10") (pin "3") (pinfunction "D_3") (pintype "passive"))
      (node (ref "R278") (pin "1") (pinfunction "1_1") (pintype "passive"))
    )
    (net (code "181") (name "/LED_GR") (class "Default")
      (node (ref "LED3") (pin "2") (pinfunction "AG_2") (pintype "passive"))
      (node (ref "R278") (pin "2") (pinfunction "2_2") (pintype "passive"))
    )
    (net (code "182") (name "/LED_LR") (class "Default")
      (node (ref "LED3") (pin "1") (pinfunction "AR_1") (pintype "passive"))
      (node (ref "R277") (pin "2") (pinfunction "2_2") (pintype "passive"))
    )
    (net (code "183") (name "/LED_R") (class "Default")
      (node (ref "IC2") (pin "H6") (pinfunction "IO_L12N_T1_MRCC_36_H6") (pintype "bidirectional"))
      (node (ref "Q7") (pin "1") (pinfunction "G_1") (pintype "passive"))
      (node (ref "R280") (pin "2") (pinfunction "2_2") (pintype "passive"))
    )
    (net (code "184") (name "/LED_RD") (class "Default")
      (node (ref "Q7") (pin "3") (pinfunction "D_3") (pintype "passive"))
      (node (ref "R277") (pin "1") (pinfunction "1_1") (pintype "passive"))
    )
    (net (code "185") (name "/MLVDS_DE_1_C") (class "Default")
      (node (ref "IC2") (pin "L7") (pinfunction "IO_25_36_L7") (pintype "bidirectional"))
    )
    (net (code "186") (name "/MLVDS_DE_2_C") (class "Default")
      (node (ref "IC2") (pin "J8") (pinfunction "IO_L7N_T1_36_J8") (pintype "bidirectional"))
    )
    (net (code "187") (name "/MLVDS_DE_3_C") (class "Default")
      (node (ref "IC2") (pin "J9") (pinfunction "IO_L7P_T1_36_J9") (pintype "bidirectional"))
    )
    (net (code "188") (name "/MLVDS_DE_4_C") (class "Default")
      (node (ref "IC2") (pin "K10") (pinfunction "IO_L6P_T0_36_K10") (pintype "bidirectional"))
    )
    (net (code "189") (name "/MLVDS_DE_5_C") (class "Default")
      (node (ref "IC2") (pin "H7") (pinfunction "IO_L12P_T1_MRCC_36_H7") (pintype "bidirectional"))
    )
    (net (code "190") (name "/MLVDS_DE_6_C") (class "Default")
      (node (ref "IC2") (pin "K12") (pinfunction "IO_L1N_T0_36_K12") (pintype "bidirectional"))
    )
    (net (code "191") (name "/MLVDS_DE_7_C") (class "Default")
      (node (ref "IC2") (pin "L12") (pinfunction "IO_L1P_T0_36_L12") (pintype "bidirectional"))
    )
    (net (code "192") (name "/MLVDS_DE_8_C") (class "Default")
      (node (ref "IC2") (pin "H12") (pinfunction "IO_0_36_H12") (pintype "bidirectional"))
    )
    (net (code "193") (name "/MMC_FPGA_MISO_C") (class "Default")
      (node (ref "IC2") (pin "R6") (pinfunction "IO_L13P_T2_MRCC_35_R6") (pintype "bidirectional"))
    )
    (net (code "194") (name "/MMC_FPGA_MOSI_C") (class "Default")
      (node (ref "IC2") (pin "P5") (pinfunction "IO_L12P_T1_MRCC_35_P5") (pintype "bidirectional"))
    )
    (net (code "195") (name "/MMC_FPGA_SCK_C") (class "Default")
      (node (ref "IC2") (pin "R5") (pinfunction "IO_L13N_T2_MRCC_35_R5") (pintype "bidirectional"))
    )
    (net (code "196") (name "/MMC_FPGA_SSEL_C") (class "Default")
      (node (ref "IC2") (pin "N4") (pinfunction "IO_L12N_T1_MRCC_35_N4") (pintype "bidirectional"))
    )
    (net (code "204") (name "GND") (class "Default")
      (node (ref "C100") (pin "2") (pinfunction "2_2") (pintype "passive"))
      (node (ref "C102") (pin "2") (pinfunction "2_2") (pintype "passive"))
      (node (ref "C111") (pin "2") (pinfunction "2_2") (pintype "passive"))
      (node (ref "C112") (pin "2") (pinfunction "2_2") (pintype "passive"))
      (node (ref "C114") (pin "2") (pinfunction "2_2") (pintype "passive"))
      (node (ref "C118") (pin "2") (pinfunction "2_2") (pintype "passive"))
      (node (ref "C120") (pin "2") (pinfunction "2_2") (pintype "passive"))
      (node (ref "C121") (pin "2") (pinfunction "2_2") (pintype "passive"))
      (node (ref "C99") (pin "2") (pinfunction "2_2") (pintype "passive"))
      (node (ref "IC25") (pin "1") (pinfunction "GND_1") (pintype "power_in"))
      (node (ref "Q10") (pin "2") (pinfunction "S_2") (pintype "passive"))
      (node (ref "Q11") (pin "2") (pinfunction "S_2") (pintype "passive"))
      (node (ref "Q7") (pin "2") (pinfunction "S_2") (pintype "passive"))
      (node (ref "R280") (pin "1") (pinfunction "1_1") (pintype "passive"))
      (node (ref "R281") (pin "1") (pinfunction "1_1") (pintype "passive"))
      (node (ref "R282") (pin "1") (pinfunction "1_1") (pintype "passive"))
    )
    (net (code "205") (name "Net-(IC25-EN)") (class "Default")
      (node (ref "C99") (pin "1") (pinfunction "1_1") (pintype "passive"))
      (node (ref "IC25") (pin "7") (pinfunction "VREF2_7") (pintype "input"))
      (node (ref "IC25") (pin "8") (pinfunction "EN_8") (pintype "input"))
      (node (ref "R179") (pin "1") (pinfunction "1_1") (pintype "passive"))
    )
    (net (code "206") (name "P3V3") (class "Default")
      (node (ref "C102") (pin "1") (pinfunction "1_1") (pintype "passive"))
      (node (ref "LED3") (pin "4") (pinfunction "CC_4") (pintype "passive"))
      (node (ref "R179") (pin "2") (pinfunction "2_2") (pintype "passive"))
    )
    (net (code "207") (name "PVADJ1") (class "Default")
      (node (ref "C100") (pin "1") (pinfunction "1_1") (pintype "passive"))
      (node (ref "IC25") (pin "2") (pinfunction "VREF1_2") (pintype "input"))
      (node (ref "R178") (pin "2") (pinfunction "2_2") (pintype "passive"))
      (node (ref "R322") (pin "1") (pinfunction "1_1") (pintype "passive"))
      (node (ref "R83") (pin "2") (pinfunction "2_2") (pintype "passive"))
    )
    (net (code "208") (name "unconnected-(IC2E-IO_0_16-PadL23)") (class "Default")
      (node (ref "IC2") (pin "L23") (pinfunction "IO_0_16_L23") (pintype "bidirectional"))
    )
    (net (code "209") (name "unconnected-(IC2E-IO_25_16-PadM26)") (class "Default")
      (node (ref "IC2") (pin "M26") (pinfunction "IO_25_16_M26") (pintype "bidirectional"))
    )
    (net (code "210") (name "unconnected-(IC2I-IO_0_34-PadY11)") (class "Default")
      (node (ref "IC2") (pin "Y11") (pinfunction "IO_0_34_Y11") (pintype "bidirectional"))
    )
    (net (code "211") (name "unconnected-(IC2I-IO_25_34-PadAB11)") (class "Default")
      (node (ref "IC2") (pin "AB11") (pinfunction "IO_25_34_AB11") (pintype "bidirectional"))
    )
    (net (code "212") (name "unconnected-(IC2I-IO_L6P_T0_34-PadW6)") (class "Default")
      (node (ref "IC2") (pin "W6") (pinfunction "IO_L6P_T0_34_W6") (pintype "bidirectional"))
    )
    (net (code "213") (name "unconnected-(IC2I-IO_L19P_T3_34-PadAA8)") (class "Default")
      (node (ref "IC2") (pin "AA8") (pinfunction "IO_L19P_T3_34_AA8") (pintype "bidirectional"))
    )
    (net (code "214") (name "unconnected-(IC2J-IO_25_35-PadU11)") (class "Default")
      (node (ref "IC2") (pin "U11") (pinfunction "IO_25_35_U11") (pintype "bidirectional"))
    )
    (net (code "215") (name "unconnected-(IC2J-IO_L2P_T0_AD12P_35-PadN9)") (class "Default")
      (node (ref "IC2") (pin "N9") (pinfunction "IO_L2P_T0_AD12P_35_N9") (pintype "bidirectional"))
    )
    (net (code "216") (name "unconnected-(IC2J-IO_L19P_T3_35-PadR8)") (class "Default")
      (node (ref "IC2") (pin "R8") (pinfunction "IO_L19P_T3_35_R8") (pintype "bidirectional"))
    )
    (net (code "217") (name "unconnected-(IC2J-IO_L21N_T3_DQS_35-PadT10)") (class "Default")
      (node (ref "IC2") (pin "T10") (pinfunction "IO_L21N_T3_DQS_35_T10") (pintype "bidirectional"))
    )
    (net (code "218") (name "unconnected-(IC2J-IO_L21P_T3_DQS_35-PadU10)") (class "Default")
      (node (ref "IC2") (pin "U10") (pinfunction "IO_L21P_T3_DQS_35_U10") (pintype "bidirectional"))
    )
    (net (code "219") (name "unconnected-(IC2J-IO_L24N_T3_35-PadT9)") (class "Default")
      (node (ref "IC2") (pin "T9") (pinfunction "IO_L24N_T3_35_T9") (pintype "bidirectional"))
    )
    (net (code "220") (name "unconnected-(IC2J-IO_L24P_T3_35-PadU9)") (class "Default")
      (node (ref "IC2") (pin "U9") (pinfunction "IO_L24P_T3_35_U9") (pintype "bidirectional"))
    )
    (net (code "221") (name "unconnected-(IC2K-IO_L4N_T0_36-PadG11)") (class "Default")
      (node (ref "IC2") (pin "G11") (pinfunction "IO_L4N_T0_36_G11") (pintype "bidirectional"))
    )
    (net (code "222") (name "unconnected-(IC2K-IO_L4P_T0_36-PadH11)") (class "Default")
      (node (ref "IC2") (pin "H11") (pinfunction "IO_L4P_T0_36_H11") (pintype "bidirectional"))
    )
    (net (code "223") (name "unconnected-(IC2K-IO_L19P_T3_36-PadL4)") (class "Default")
      (node (ref "IC2") (pin "L4") (pinfunction "IO_L19P_T3_36_L4") (pintype "bidirectional"))
    )
  )
)
